# Buzzwad_Buoy_Faith_DEA.net
KiCad netlist of a schematic drawn in EAGLE
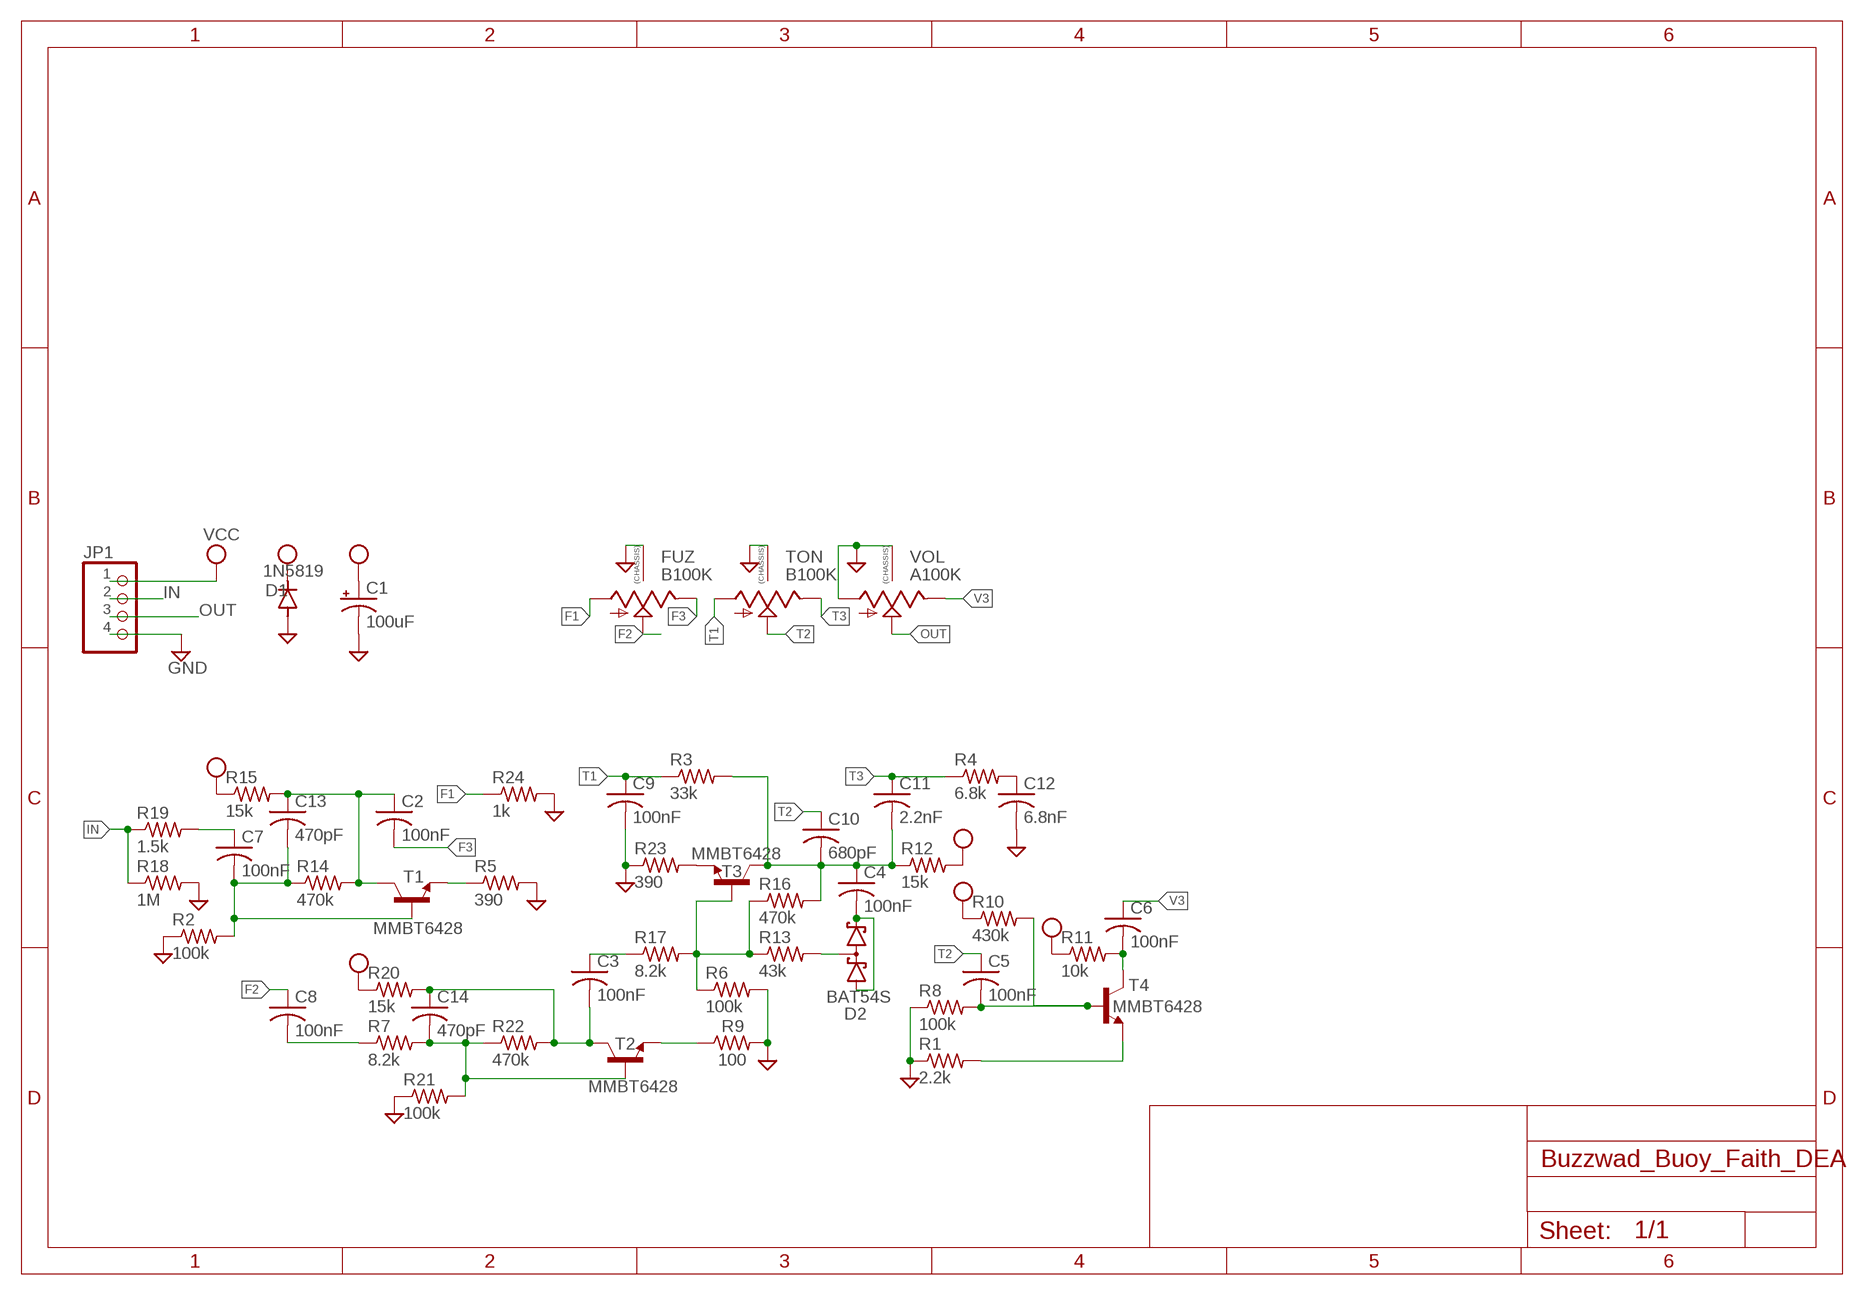
[diagram p0: schematic, sheet 1]

(export (version "E")
  (design (tool "Eeschema 10.0.6"))
  (components
    (comp (ref "C1")
      (value "100uF")
      (footprint "eagle-import:PAN_B_SMD+THRU")
      (libsource (lib "eagle-import") (part "CAP_SMD+THRUPAN_B"))
    )
    (comp (ref "C2")
      (value "100nF")
      (footprint "eagle-import:C0402")
      (libsource (lib "eagle-import") (part "C-USC0402"))
    )
    (comp (ref "C3")
      (value "100nF")
      (footprint "eagle-import:C0402")
      (libsource (lib "eagle-import") (part "C-USC0402"))
    )
    (comp (ref "C4")
      (value "100nF")
      (footprint "eagle-import:C0402")
      (libsource (lib "eagle-import") (part "C-USC0402"))
    )
    (comp (ref "C5")
      (value "100nF")
      (footprint "eagle-import:C0402")
      (libsource (lib "eagle-import") (part "C-USC0402"))
    )
    (comp (ref "C6")
      (value "100nF")
      (footprint "eagle-import:C0402")
      (libsource (lib "eagle-import") (part "C-USC0402"))
    )
    (comp (ref "C7")
      (value "100nF")
      (footprint "eagle-import:C0402")
      (libsource (lib "eagle-import") (part "C-USC0402"))
    )
    (comp (ref "C8")
      (value "100nF")
      (footprint "eagle-import:C0402")
      (libsource (lib "eagle-import") (part "C-USC0402"))
    )
    (comp (ref "C9")
      (value "100nF")
      (footprint "eagle-import:C0402")
      (libsource (lib "eagle-import") (part "C-USC0402"))
    )
    (comp (ref "C10")
      (value "680pF")
      (footprint "eagle-import:C0402")
      (libsource (lib "eagle-import") (part "C-USC0402"))
    )
    (comp (ref "C11")
      (value "2.2nF")
      (footprint "eagle-import:C0402")
      (libsource (lib "eagle-import") (part "C-USC0402"))
    )
    (comp (ref "C12")
      (value "6.8nF")
      (footprint "eagle-import:C0402")
      (libsource (lib "eagle-import") (part "C-USC0402"))
    )
    (comp (ref "C13")
      (value "470pF")
      (footprint "eagle-import:C0402")
      (libsource (lib "eagle-import") (part "C-USC0402"))
    )
    (comp (ref "C14")
      (value "470pF")
      (footprint "eagle-import:C0402")
      (libsource (lib "eagle-import") (part "C-USC0402"))
    )
    (comp (ref "D1")
      (value "1N5819")
      (footprint "eagle-import:SOD123")
      (libsource (lib "eagle-import") (part "DIODE-SOD123"))
    )
    (comp (ref "D2")
      (value "BAT54S")
      (footprint "eagle-import:SOT23")
      (libsource (lib "eagle-import") (part "BAT54S"))
    )
    (comp (ref "FUZ")
      (value "B100K")
      (footprint "eagle-import:9MM_SNAP-IN_POT")
      (libsource (lib "eagle-import") (part "9MM_SNAP-IN_POT_CHASSIS"))
    )
    (comp (ref "JP1")
      (value "PINHD-1X4")
      (footprint "eagle-import:1X04")
      (libsource (lib "eagle-import") (part "PINHD-1X4"))
    )
    (comp (ref "R1")
      (value "2.2k")
      (footprint "eagle-import:R0402")
      (libsource (lib "eagle-import") (part "R-US_R0402"))
    )
    (comp (ref "R2")
      (value "100k")
      (footprint "eagle-import:R0402")
      (libsource (lib "eagle-import") (part "R-US_R0402"))
    )
    (comp (ref "R3")
      (value "33k")
      (footprint "eagle-import:R0402")
      (libsource (lib "eagle-import") (part "R-US_R0402"))
    )
    (comp (ref "R4")
      (value "6.8k")
      (footprint "eagle-import:R0402")
      (libsource (lib "eagle-import") (part "R-US_R0402"))
    )
    (comp (ref "R5")
      (value "390")
      (footprint "eagle-import:R0402")
      (libsource (lib "eagle-import") (part "R-US_R0402"))
    )
    (comp (ref "R6")
      (value "100k")
      (footprint "eagle-import:R0402")
      (libsource (lib "eagle-import") (part "R-US_R0402"))
    )
    (comp (ref "R7")
      (value "8.2k")
      (footprint "eagle-import:R0402")
      (libsource (lib "eagle-import") (part "R-US_R0402"))
    )
    (comp (ref "R8")
      (value "100k")
      (footprint "eagle-import:R0402")
      (libsource (lib "eagle-import") (part "R-US_R0402"))
    )
    (comp (ref "R9")
      (value "100")
      (footprint "eagle-import:R0402")
      (libsource (lib "eagle-import") (part "R-US_R0402"))
    )
    (comp (ref "R10")
      (value "430k")
      (footprint "eagle-import:R0402")
      (libsource (lib "eagle-import") (part "R-US_R0402"))
    )
    (comp (ref "R11")
      (value "10k")
      (footprint "eagle-import:R0402")
      (libsource (lib "eagle-import") (part "R-US_R0402"))
    )
    (comp (ref "R12")
      (value "15k")
      (footprint "eagle-import:R0402")
      (libsource (lib "eagle-import") (part "R-US_R0402"))
    )
    (comp (ref "R13")
      (value "43k")
      (footprint "eagle-import:R0402")
      (libsource (lib "eagle-import") (part "R-US_R0402"))
    )
    (comp (ref "R14")
      (value "470k")
      (footprint "eagle-import:R0402")
      (libsource (lib "eagle-import") (part "R-US_R0402"))
    )
    (comp (ref "R15")
      (value "15k")
      (footprint "eagle-import:R0402")
      (libsource (lib "eagle-import") (part "R-US_R0402"))
    )
    (comp (ref "R16")
      (value "470k")
      (footprint "eagle-import:R0402")
      (libsource (lib "eagle-import") (part "R-US_R0402"))
    )
    (comp (ref "R17")
      (value "8.2k")
      (footprint "eagle-import:R0402")
      (libsource (lib "eagle-import") (part "R-US_R0402"))
    )
    (comp (ref "R18")
      (value "1M")
      (footprint "eagle-import:R0402")
      (libsource (lib "eagle-import") (part "R-US_R0402"))
    )
    (comp (ref "R19")
      (value "1.5k")
      (footprint "eagle-import:R0402")
      (libsource (lib "eagle-import") (part "R-US_R0402"))
    )
    (comp (ref "R20")
      (value "15k")
      (footprint "eagle-import:R0402")
      (libsource (lib "eagle-import") (part "R-US_R0402"))
    )
    (comp (ref "R21")
      (value "100k")
      (footprint "eagle-import:R0402")
      (libsource (lib "eagle-import") (part "R-US_R0402"))
    )
    (comp (ref "R22")
      (value "470k")
      (footprint "eagle-import:R0402")
      (libsource (lib "eagle-import") (part "R-US_R0402"))
    )
    (comp (ref "R23")
      (value "390")
      (footprint "eagle-import:R0402")
      (libsource (lib "eagle-import") (part "R-US_R0402"))
    )
    (comp (ref "R24")
      (value "1k")
      (footprint "eagle-import:R0402")
      (libsource (lib "eagle-import") (part "R-US_R0402"))
    )
    (comp (ref "T1")
      (value "MMBT6428")
      (footprint "eagle-import:SOT23-BEC")
      (libsource (lib "eagle-import") (part "-NPN-SOT23-BECBC808"))
    )
    (comp (ref "T2")
      (value "MMBT6428")
      (footprint "eagle-import:SOT23-BEC")
      (libsource (lib "eagle-import") (part "-NPN-SOT23-BECBC808"))
    )
    (comp (ref "T3")
      (value "MMBT6428")
      (footprint "eagle-import:SOT23-BEC")
      (libsource (lib "eagle-import") (part "-NPN-SOT23-BECBC808"))
    )
    (comp (ref "T4")
      (value "MMBT6428")
      (footprint "eagle-import:SOT23-BEC")
      (libsource (lib "eagle-import") (part "-NPN-SOT23-BECBC808"))
    )
    (comp (ref "TON")
      (value "B100K")
      (footprint "eagle-import:9MM_SNAP-IN_POT")
      (libsource (lib "eagle-import") (part "9MM_SNAP-IN_POT_CHASSIS"))
    )
    (comp (ref "VOL")
      (value "A100K")
      (footprint "eagle-import:9MM_SNAP-IN_POT")
      (libsource (lib "eagle-import") (part "9MM_SNAP-IN_POT_CHASSIS"))
    )
  )
  (nets
    (net (code "1") (name "F1") (class "Default")
      (node (ref "FUZ") (pin "1") (pinfunction "A_1") (pintype "passive"))
      (node (ref "R24") (pin "1") (pinfunction "1_1") (pintype "passive"))
    )
    (net (code "2") (name "F2") (class "Default")
      (node (ref "C8") (pin "1") (pinfunction "1_1") (pintype "passive"))
      (node (ref "FUZ") (pin "2") (pinfunction "S_2") (pintype "passive"))
    )
    (net (code "3") (name "F3") (class "Default")
      (node (ref "C2") (pin "2") (pinfunction "2_2") (pintype "passive"))
      (node (ref "FUZ") (pin "3") (pinfunction "E_3") (pintype "passive"))
    )
    (net (code "4") (name "GND") (class "Default")
      (node (ref "C1") (pin "-") (pinfunction "-_-") (pintype "passive"))
      (node (ref "C1") (pin "--") (pinfunction "-_--") (pintype "passive"))
      (node (ref "C12") (pin "2") (pinfunction "2_2") (pintype "passive"))
      (node (ref "C9") (pin "2") (pinfunction "2_2") (pintype "passive"))
      (node (ref "D1") (pin "A") (pinfunction "A_A") (pintype "passive"))
      (node (ref "FUZ") (pin "CHASSIS1") (pinfunction "P$1_CHASSIS1") (pintype "passive"))
      (node (ref "FUZ") (pin "CHASSIS2") (pinfunction "P$1_CHASSIS2") (pintype "passive"))
      (node (ref "JP1") (pin "4") (pinfunction "4_4") (pintype "passive"))
      (node (ref "R1") (pin "1") (pinfunction "1_1") (pintype "passive"))
      (node (ref "R18") (pin "2") (pinfunction "2_2") (pintype "passive"))
      (node (ref "R2") (pin "1") (pinfunction "1_1") (pintype "passive"))
      (node (ref "R21") (pin "1") (pinfunction "1_1") (pintype "passive"))
      (node (ref "R23") (pin "1") (pinfunction "1_1") (pintype "passive"))
      (node (ref "R24") (pin "2") (pinfunction "2_2") (pintype "passive"))
      (node (ref "R5") (pin "2") (pinfunction "2_2") (pintype "passive"))
      (node (ref "R6") (pin "2") (pinfunction "2_2") (pintype "passive"))
      (node (ref "R8") (pin "1") (pinfunction "1_1") (pintype "passive"))
      (node (ref "R9") (pin "2") (pinfunction "2_2") (pintype "passive"))
      (node (ref "TON") (pin "CHASSIS1") (pinfunction "P$1_CHASSIS1") (pintype "passive"))
      (node (ref "TON") (pin "CHASSIS2") (pinfunction "P$1_CHASSIS2") (pintype "passive"))
      (node (ref "VOL") (pin "1") (pinfunction "A_1") (pintype "passive"))
      (node (ref "VOL") (pin "CHASSIS1") (pinfunction "P$1_CHASSIS1") (pintype "passive"))
      (node (ref "VOL") (pin "CHASSIS2") (pinfunction "P$1_CHASSIS2") (pintype "passive"))
    )
    (net (code "5") (name "IN") (class "Default")
      (node (ref "JP1") (pin "2") (pinfunction "2_2") (pintype "passive"))
      (node (ref "R18") (pin "1") (pinfunction "1_1") (pintype "passive"))
      (node (ref "R19") (pin "1") (pinfunction "1_1") (pintype "passive"))
    )
    (net (code "6") (name "Net-(C3-Pad1)") (class "Default")
      (node (ref "C3") (pin "1") (pinfunction "1_1") (pintype "passive"))
      (node (ref "R17") (pin "1") (pinfunction "1_1") (pintype "passive"))
    )
    (net (code "7") (name "Net-(C5-Pad2)") (class "Default")
      (node (ref "C5") (pin "2") (pinfunction "2_2") (pintype "passive"))
      (node (ref "R10") (pin "2") (pinfunction "2_2") (pintype "passive"))
      (node (ref "R8") (pin "2") (pinfunction "2_2") (pintype "passive"))
      (node (ref "T4") (pin "B") (pinfunction "B_B") (pintype "passive"))
    )
    (net (code "8") (name "Net-(C6-Pad2)") (class "Default")
      (node (ref "C6") (pin "2") (pinfunction "2_2") (pintype "passive"))
      (node (ref "R11") (pin "2") (pinfunction "2_2") (pintype "passive"))
      (node (ref "T4") (pin "C") (pinfunction "C_C") (pintype "passive"))
    )
    (net (code "9") (name "Net-(C7-Pad1)") (class "Default")
      (node (ref "C7") (pin "1") (pinfunction "1_1") (pintype "passive"))
      (node (ref "R19") (pin "2") (pinfunction "2_2") (pintype "passive"))
    )
    (net (code "10") (name "Net-(C8-Pad2)") (class "Default")
      (node (ref "C8") (pin "2") (pinfunction "2_2") (pintype "passive"))
      (node (ref "R7") (pin "1") (pinfunction "1_1") (pintype "passive"))
    )
    (net (code "11") (name "Net-(C10-Pad2)") (class "Default")
      (node (ref "C10") (pin "2") (pinfunction "2_2") (pintype "passive"))
      (node (ref "C11") (pin "2") (pinfunction "2_2") (pintype "passive"))
      (node (ref "C4") (pin "1") (pinfunction "1_1") (pintype "passive"))
      (node (ref "R12") (pin "1") (pinfunction "1_1") (pintype "passive"))
      (node (ref "R16") (pin "2") (pinfunction "2_2") (pintype "passive"))
      (node (ref "R3") (pin "2") (pinfunction "2_2") (pintype "passive"))
      (node (ref "T3") (pin "C") (pinfunction "C_C") (pintype "passive"))
    )
    (net (code "12") (name "Net-(C12-Pad1)") (class "Default")
      (node (ref "C12") (pin "1") (pinfunction "1_1") (pintype "passive"))
      (node (ref "R4") (pin "2") (pinfunction "2_2") (pintype "passive"))
    )
    (net (code "13") (name "Net-(C13-Pad1)") (class "Default")
      (node (ref "C13") (pin "1") (pinfunction "1_1") (pintype "passive"))
      (node (ref "C2") (pin "1") (pinfunction "1_1") (pintype "passive"))
      (node (ref "R14") (pin "2") (pinfunction "2_2") (pintype "passive"))
      (node (ref "R15") (pin "2") (pinfunction "2_2") (pintype "passive"))
      (node (ref "T1") (pin "C") (pinfunction "C_C") (pintype "passive"))
    )
    (net (code "14") (name "Net-(C13-Pad2)") (class "Default")
      (node (ref "C13") (pin "2") (pinfunction "2_2") (pintype "passive"))
      (node (ref "C7") (pin "2") (pinfunction "2_2") (pintype "passive"))
      (node (ref "R14") (pin "1") (pinfunction "1_1") (pintype "passive"))
      (node (ref "R2") (pin "2") (pinfunction "2_2") (pintype "passive"))
      (node (ref "T1") (pin "B") (pinfunction "B_B") (pintype "passive"))
    )
    (net (code "15") (name "Net-(C14-Pad1)") (class "Default")
      (node (ref "C14") (pin "1") (pinfunction "1_1") (pintype "passive"))
      (node (ref "C3") (pin "2") (pinfunction "2_2") (pintype "passive"))
      (node (ref "R20") (pin "2") (pinfunction "2_2") (pintype "passive"))
      (node (ref "R22") (pin "2") (pinfunction "2_2") (pintype "passive"))
      (node (ref "T2") (pin "C") (pinfunction "C_C") (pintype "passive"))
    )
    (net (code "16") (name "Net-(C14-Pad2)") (class "Default")
      (node (ref "C14") (pin "2") (pinfunction "2_2") (pintype "passive"))
      (node (ref "R21") (pin "2") (pinfunction "2_2") (pintype "passive"))
      (node (ref "R22") (pin "1") (pinfunction "1_1") (pintype "passive"))
      (node (ref "R7") (pin "2") (pinfunction "2_2") (pintype "passive"))
      (node (ref "T2") (pin "B") (pinfunction "B_B") (pintype "passive"))
    )
    (net (code "17") (name "Net-(D2-A1)") (class "Default")
      (node (ref "C4") (pin "2") (pinfunction "2_2") (pintype "passive"))
      (node (ref "D2") (pin "1") (pinfunction "A1_1") (pintype "passive"))
      (node (ref "D2") (pin "2") (pinfunction "C2_2") (pintype "passive"))
    )
    (net (code "18") (name "Net-(D2-C1A2)") (class "Default")
      (node (ref "D2") (pin "3") (pinfunction "C1A2_3") (pintype "passive"))
      (node (ref "R13") (pin "2") (pinfunction "2_2") (pintype "passive"))
    )
    (net (code "19") (name "Net-(R1-Pad2)") (class "Default")
      (node (ref "R1") (pin "2") (pinfunction "2_2") (pintype "passive"))
      (node (ref "T4") (pin "E") (pinfunction "E_E") (pintype "passive"))
    )
    (net (code "20") (name "Net-(R5-Pad1)") (class "Default")
      (node (ref "R5") (pin "1") (pinfunction "1_1") (pintype "passive"))
      (node (ref "T1") (pin "E") (pinfunction "E_E") (pintype "passive"))
    )
    (net (code "21") (name "Net-(R9-Pad1)") (class "Default")
      (node (ref "R9") (pin "1") (pinfunction "1_1") (pintype "passive"))
      (node (ref "T2") (pin "E") (pinfunction "E_E") (pintype "passive"))
    )
    (net (code "22") (name "Net-(R13-Pad1)") (class "Default")
      (node (ref "R13") (pin "1") (pinfunction "1_1") (pintype "passive"))
      (node (ref "R16") (pin "1") (pinfunction "1_1") (pintype "passive"))
      (node (ref "R17") (pin "2") (pinfunction "2_2") (pintype "passive"))
      (node (ref "R6") (pin "1") (pinfunction "1_1") (pintype "passive"))
      (node (ref "T3") (pin "B") (pinfunction "B_B") (pintype "passive"))
    )
    (net (code "23") (name "Net-(R23-Pad2)") (class "Default")
      (node (ref "R23") (pin "2") (pinfunction "2_2") (pintype "passive"))
      (node (ref "T3") (pin "E") (pinfunction "E_E") (pintype "passive"))
    )
    (net (code "24") (name "OUT") (class "Default")
      (node (ref "JP1") (pin "3") (pinfunction "3_3") (pintype "passive"))
      (node (ref "VOL") (pin "2") (pinfunction "S_2") (pintype "passive"))
    )
    (net (code "25") (name "T1") (class "Default")
      (node (ref "C9") (pin "1") (pinfunction "1_1") (pintype "passive"))
      (node (ref "R3") (pin "1") (pinfunction "1_1") (pintype "passive"))
      (node (ref "TON") (pin "1") (pinfunction "A_1") (pintype "passive"))
    )
    (net (code "26") (name "T2") (class "Default")
      (node (ref "C10") (pin "1") (pinfunction "1_1") (pintype "passive"))
      (node (ref "C5") (pin "1") (pinfunction "1_1") (pintype "passive"))
      (node (ref "TON") (pin "2") (pinfunction "S_2") (pintype "passive"))
    )
    (net (code "27") (name "T3") (class "Default")
      (node (ref "C11") (pin "1") (pinfunction "1_1") (pintype "passive"))
      (node (ref "R4") (pin "1") (pinfunction "1_1") (pintype "passive"))
      (node (ref "TON") (pin "3") (pinfunction "E_3") (pintype "passive"))
    )
    (net (code "28") (name "V3") (class "Default")
      (node (ref "C6") (pin "1") (pinfunction "1_1") (pintype "passive"))
      (node (ref "VOL") (pin "3") (pinfunction "E_3") (pintype "passive"))
    )
    (net (code "29") (name "VCC") (class "Default")
      (node (ref "C1") (pin "+") (pinfunction "+_+") (pintype "passive"))
      (node (ref "C1") (pin "++") (pinfunction "+_++") (pintype "passive"))
      (node (ref "D1") (pin "C") (pinfunction "C_C") (pintype "passive"))
      (node (ref "JP1") (pin "1") (pinfunction "1_1") (pintype "passive"))
      (node (ref "R10") (pin "1") (pinfunction "1_1") (pintype "passive"))
      (node (ref "R11") (pin "1") (pinfunction "1_1") (pintype "passive"))
      (node (ref "R12") (pin "2") (pinfunction "2_2") (pintype "passive"))
      (node (ref "R15") (pin "1") (pinfunction "1_1") (pintype "passive"))
      (node (ref "R20") (pin "1") (pinfunction "1_1") (pintype "passive"))
    )
  )
)
